# 03-CTRL1-ps2-blueretro.net
KiCad netlist of a schematic drawn in Altium Designer
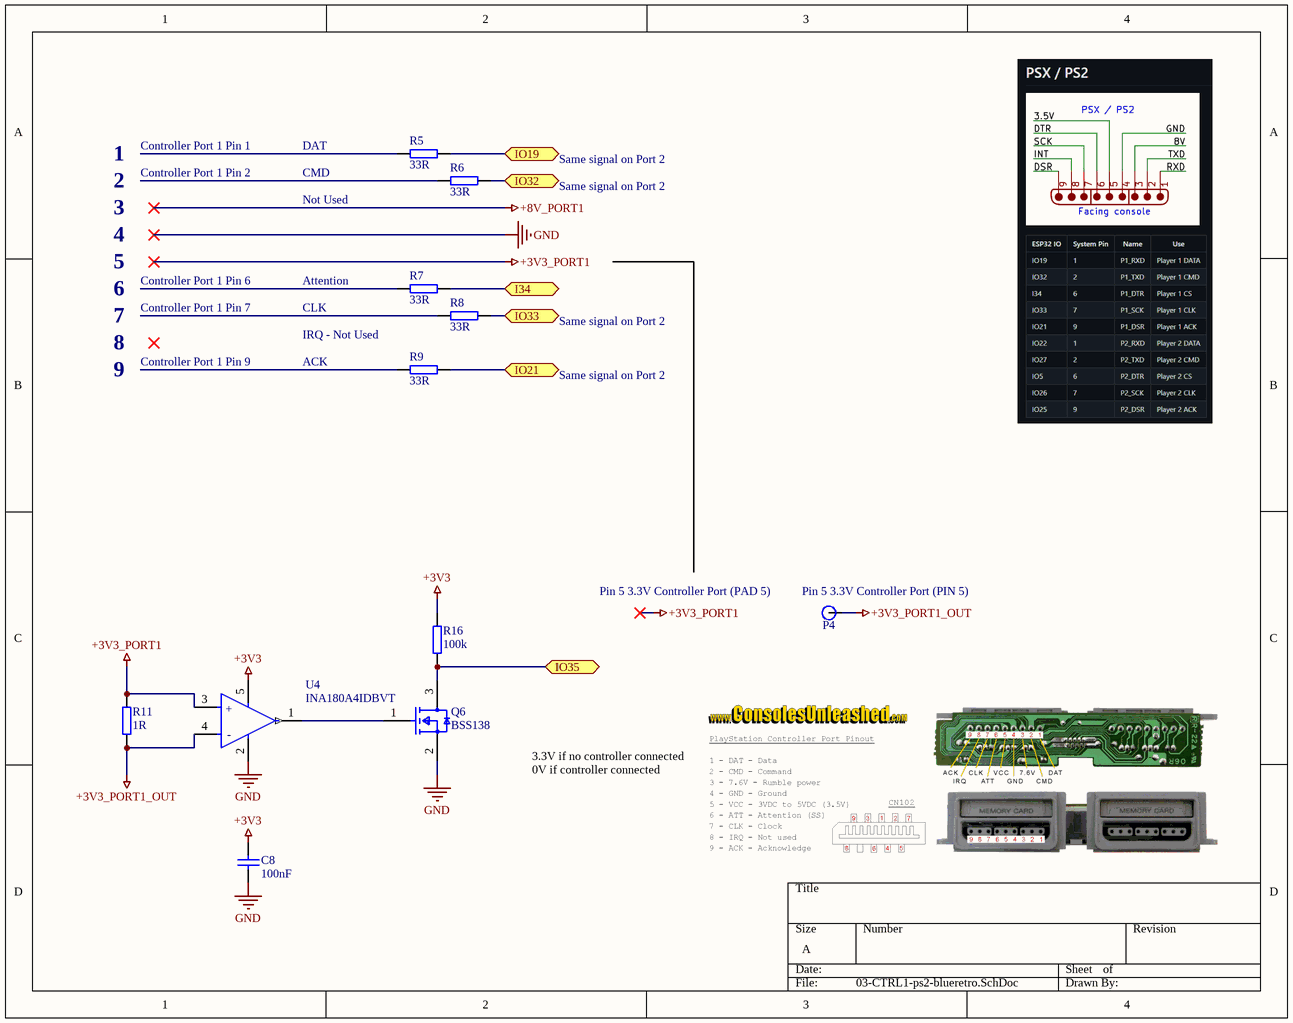
[diagram p0: 03-CTRL1-ps2-blueretro.SchDoc]

(export (version "E")
  (design (tool "Eeschema 10.0.6"))
  (components
    (comp (ref "C8")
      (value "100nF")
      (footprint "res_0402")
      (fields (field (name "Comment") "cap_0402"))
      (libsource (lib "mycomponents") (part "cap_0402"))
    )
    (comp (ref "P4")
      (value "Solder_Contact_2mm")
      (footprint "SINGLE_SOLDER_CON")
      (libsource (lib "mycomponents") (part "Solder_Contact_2mm"))
    )
    (comp (ref "Q6")
      (value "BSS138")
      (footprint "FP-318-08-IPC_B")
      (description "MOSFET N-CH 50V 220MA SOT-23")
      (libsource (lib "Altium Content Vault") (part "3b9c635fedb024a5347a57b145af9cc"))
    )
    (comp (ref "R5")
      (value "33R")
      (footprint "res_0402")
      (fields (field (name "Comment") "res_0402"))
      (libsource (lib "mycomponents") (part "res_0402"))
    )
    (comp (ref "R6")
      (value "33R")
      (footprint "res_0402")
      (fields (field (name "Comment") "res_0402"))
      (libsource (lib "mycomponents") (part "res_0402"))
    )
    (comp (ref "R7")
      (value "33R")
      (footprint "res_0402")
      (fields (field (name "Comment") "res_0402"))
      (libsource (lib "mycomponents") (part "res_0402"))
    )
    (comp (ref "R8")
      (value "33R")
      (footprint "res_0402")
      (fields (field (name "Comment") "res_0402"))
      (libsource (lib "mycomponents") (part "res_0402"))
    )
    (comp (ref "R9")
      (value "33R")
      (footprint "res_0402")
      (fields (field (name "Comment") "res_0402"))
      (libsource (lib "mycomponents") (part "res_0402"))
    )
    (comp (ref "R11")
      (value "1R")
      (footprint "res_0402")
      (fields (field (name "Comment") "res_0402"))
      (libsource (lib "mycomponents") (part "res_0402"))
    )
    (comp (ref "R16")
      (value "100k")
      (footprint "res_0603")
      (fields (field (name "Comment") "res_0603"))
      (libsource (lib "mycomponents") (part "res_0603"))
    )
    (comp (ref "U4")
      (value "INA180A4IDBVT")
      (footprint "FP-DBV0005A-MFG")
      (description "IC CURR SENSE 1 CIRCUIT SOT23-5")
      (fields
        (field (name "OCTOPART") "https://octopart.com/ina180a4idbvt-texas+instruments-81856280")
        (field (name "MANUFACTURER") "Texas Instruments")
      )
      (libsource (lib "Altium Content Vault") (part "0a55cf1a948ad01a3239aec1b7efad0"))
    )
  )
  (nets
    (net (code "1") (name "+3V3") (class "Default")
      (node (ref "C8") (pin "1") (pinfunction "1_1") (pintype "passive"))
      (node (ref "R16") (pin "2") (pinfunction "2_2") (pintype "passive"))
      (node (ref "U4") (pin "5") (pinfunction "VS_5") (pintype "power_in"))
    )
    (net (code "2") (name "+3V3_PORT1") (class "Default")
      (node (ref "R11") (pin "1") (pinfunction "1_1") (pintype "passive"))
      (node (ref "U4") (pin "3") (pinfunction "IN+_3") (pintype "tri_state"))
    )
    (net (code "3") (name "+3V3_PORT1_OUT") (class "Default")
      (node (ref "P4") (pin "1") (pinfunction "1_1") (pintype "passive"))
      (node (ref "R11") (pin "2") (pinfunction "2_2") (pintype "passive"))
      (node (ref "U4") (pin "4") (pinfunction "IN-_4") (pintype "tri_state"))
    )
    (net (code "5") (name "/I34") (class "Default")
      (node (ref "R7") (pin "1") (pinfunction "1_1") (pintype "passive"))
    )
    (net (code "6") (name "/IO19") (class "Default")
      (node (ref "R5") (pin "1") (pinfunction "1_1") (pintype "passive"))
    )
    (net (code "7") (name "/IO21") (class "Default")
      (node (ref "R9") (pin "1") (pinfunction "1_1") (pintype "passive"))
    )
    (net (code "8") (name "/IO32") (class "Default")
      (node (ref "R6") (pin "1") (pinfunction "1_1") (pintype "passive"))
    )
    (net (code "9") (name "/IO33") (class "Default")
      (node (ref "R8") (pin "1") (pinfunction "1_1") (pintype "passive"))
    )
    (net (code "10") (name "/IO35") (class "Default")
      (node (ref "Q6") (pin "3") (pinfunction "D_3") (pintype "passive"))
      (node (ref "R16") (pin "1") (pinfunction "1_1") (pintype "passive"))
    )
    (net (code "11") (name "GND") (class "Default")
      (node (ref "C8") (pin "2") (pinfunction "2_2") (pintype "passive"))
      (node (ref "Q6") (pin "2") (pinfunction "S_2") (pintype "passive"))
      (node (ref "U4") (pin "2") (pinfunction "GND_2") (pintype "power_in"))
    )
    (net (code "12") (name "Net-(Q6-G)") (class "Default")
      (node (ref "Q6") (pin "1") (pinfunction "G_1") (pintype "passive"))
      (node (ref "U4") (pin "1") (pinfunction "OUT_1") (pintype "output"))
    )
    (net (code "13") (name "unconnected-(R5-Pad2)") (class "Default")
      (node (ref "R5") (pin "2") (pinfunction "2_2") (pintype "passive"))
    )
    (net (code "14") (name "unconnected-(R6-Pad2)") (class "Default")
      (node (ref "R6") (pin "2") (pinfunction "2_2") (pintype "passive"))
    )
    (net (code "15") (name "unconnected-(R7-Pad2)") (class "Default")
      (node (ref "R7") (pin "2") (pinfunction "2_2") (pintype "passive"))
    )
    (net (code "16") (name "unconnected-(R8-Pad2)") (class "Default")
      (node (ref "R8") (pin "2") (pinfunction "2_2") (pintype "passive"))
    )
    (net (code "17") (name "unconnected-(R9-Pad2)") (class "Default")
      (node (ref "R9") (pin "2") (pinfunction "2_2") (pintype "passive"))
    )
  )
)
